# usb_hub_asic.net
KiCad netlist of a schematic drawn in EAGLE
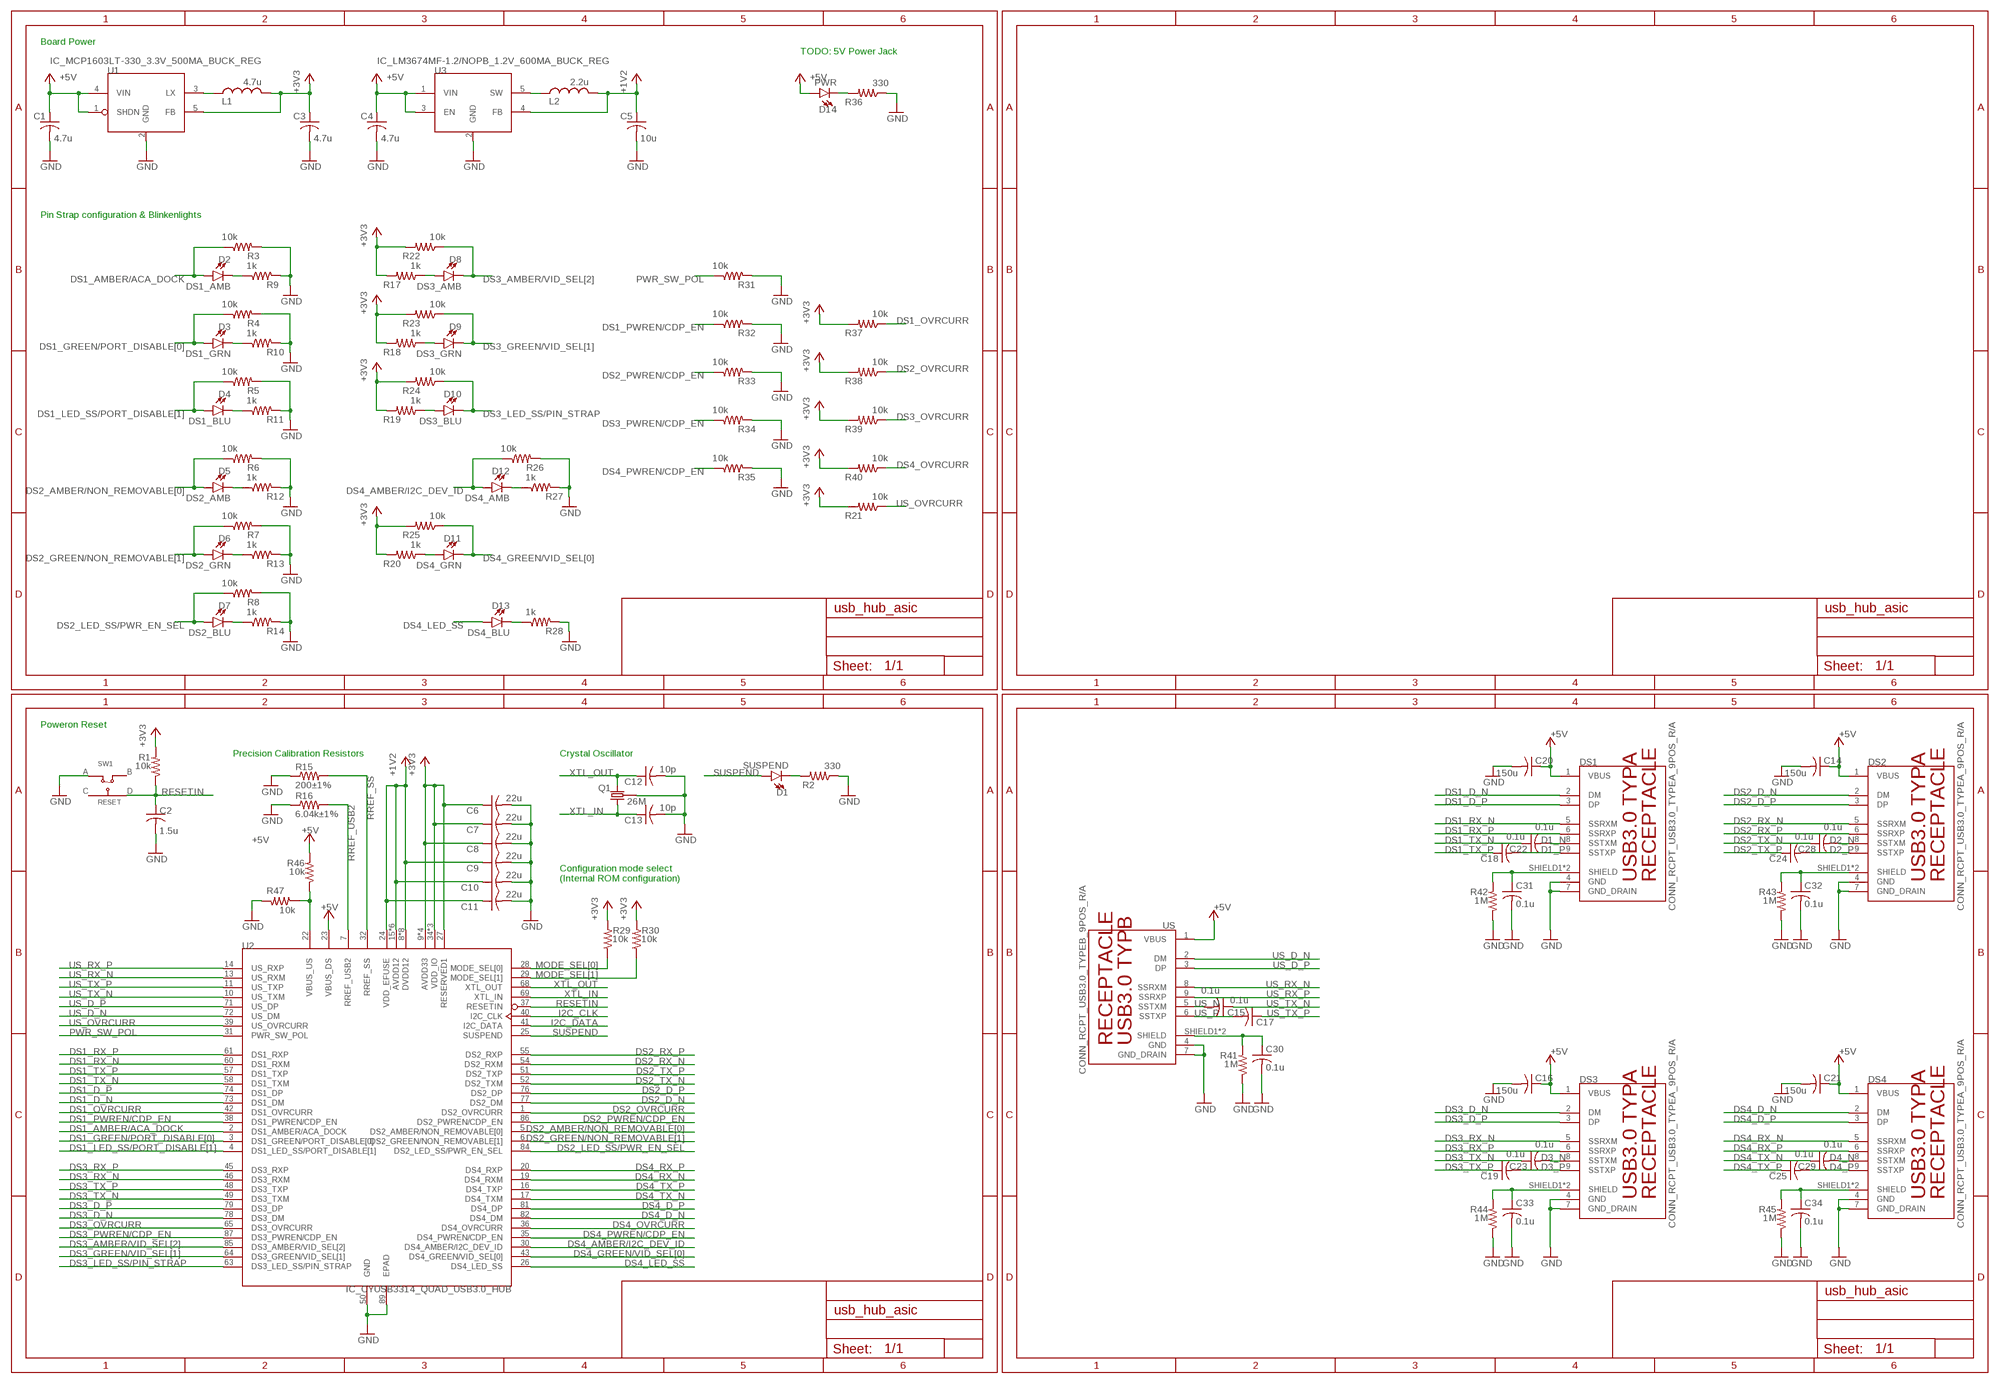
[diagram p0: schematic, sheet 1]

(export (version "E")
  (design (tool "Eeschema 10.0.6"))
  (components
    (comp (ref "C1")
      (value "4.7u")
      (footprint "eagle-import:C0603")
      (libsource (lib "eagle-import") (part "C-USC0603"))
    )
    (comp (ref "C2")
      (value "1.5u")
      (footprint "eagle-import:C0603")
      (libsource (lib "eagle-import") (part "C-USC0603"))
    )
    (comp (ref "C3")
      (value "4.7u")
      (footprint "eagle-import:C0603")
      (libsource (lib "eagle-import") (part "C-USC0603"))
    )
    (comp (ref "C4")
      (value "4.7u")
      (footprint "eagle-import:C0603")
      (libsource (lib "eagle-import") (part "C-USC0603"))
    )
    (comp (ref "C5")
      (value "10u")
      (footprint "eagle-import:C0805")
      (libsource (lib "eagle-import") (part "C-USC0805"))
    )
    (comp (ref "C6")
      (value "22u")
      (footprint "eagle-import:C0603")
      (libsource (lib "eagle-import") (part "C-USC0603"))
    )
    (comp (ref "C7")
      (value "22u")
      (footprint "eagle-import:C0603")
      (libsource (lib "eagle-import") (part "C-USC0603"))
    )
    (comp (ref "C8")
      (value "22u")
      (footprint "eagle-import:C0603")
      (libsource (lib "eagle-import") (part "C-USC0603"))
    )
    (comp (ref "C9")
      (value "22u")
      (footprint "eagle-import:C0603")
      (libsource (lib "eagle-import") (part "C-USC0603"))
    )
    (comp (ref "C10")
      (value "22u")
      (footprint "eagle-import:C0603")
      (libsource (lib "eagle-import") (part "C-USC0603"))
    )
    (comp (ref "C11")
      (value "22u")
      (footprint "eagle-import:C0603")
      (libsource (lib "eagle-import") (part "C-USC0603"))
    )
    (comp (ref "C12")
      (value "10p")
      (footprint "eagle-import:C0603")
      (libsource (lib "eagle-import") (part "C-USC0603"))
    )
    (comp (ref "C13")
      (value "10p")
      (footprint "eagle-import:C0603")
      (libsource (lib "eagle-import") (part "C-USC0603"))
    )
    (comp (ref "C14")
      (value "150u")
      (footprint "eagle-import:C1210K")
      (libsource (lib "eagle-import") (part "C-USC1210K"))
    )
    (comp (ref "C15")
      (value "0.1u")
      (footprint "eagle-import:C0603")
      (libsource (lib "eagle-import") (part "C-USC0603"))
    )
    (comp (ref "C16")
      (value "150u")
      (footprint "eagle-import:C1210K")
      (libsource (lib "eagle-import") (part "C-USC1210K"))
    )
    (comp (ref "C17")
      (value "0.1u")
      (footprint "eagle-import:C0603")
      (libsource (lib "eagle-import") (part "C-USC0603"))
    )
    (comp (ref "C18")
      (value "0.1u")
      (footprint "eagle-import:C0603")
      (libsource (lib "eagle-import") (part "C-USC0603"))
    )
    (comp (ref "C19")
      (value "0.1u")
      (footprint "eagle-import:C0603")
      (libsource (lib "eagle-import") (part "C-USC0603"))
    )
    (comp (ref "C20")
      (value "150u")
      (footprint "eagle-import:C1210K")
      (libsource (lib "eagle-import") (part "C-USC1210K"))
    )
    (comp (ref "C21")
      (value "150u")
      (footprint "eagle-import:C1210K")
      (libsource (lib "eagle-import") (part "C-USC1210K"))
    )
    (comp (ref "C22")
      (value "0.1u")
      (footprint "eagle-import:C0603")
      (libsource (lib "eagle-import") (part "C-USC0603"))
    )
    (comp (ref "C23")
      (value "0.1u")
      (footprint "eagle-import:C0603")
      (libsource (lib "eagle-import") (part "C-USC0603"))
    )
    (comp (ref "C24")
      (value "0.1u")
      (footprint "eagle-import:C0603")
      (libsource (lib "eagle-import") (part "C-USC0603"))
    )
    (comp (ref "C25")
      (value "0.1u")
      (footprint "eagle-import:C0603")
      (libsource (lib "eagle-import") (part "C-USC0603"))
    )
    (comp (ref "C28")
      (value "0.1u")
      (footprint "eagle-import:C0603")
      (libsource (lib "eagle-import") (part "C-USC0603"))
    )
    (comp (ref "C29")
      (value "0.1u")
      (footprint "eagle-import:C0603")
      (libsource (lib "eagle-import") (part "C-USC0603"))
    )
    (comp (ref "C30")
      (value "0.1u")
      (footprint "eagle-import:C0603")
      (libsource (lib "eagle-import") (part "C-USC0603"))
    )
    (comp (ref "C31")
      (value "0.1u")
      (footprint "eagle-import:C0603")
      (libsource (lib "eagle-import") (part "C-USC0603"))
    )
    (comp (ref "C32")
      (value "0.1u")
      (footprint "eagle-import:C0603")
      (libsource (lib "eagle-import") (part "C-USC0603"))
    )
    (comp (ref "C33")
      (value "0.1u")
      (footprint "eagle-import:C0603")
      (libsource (lib "eagle-import") (part "C-USC0603"))
    )
    (comp (ref "C34")
      (value "0.1u")
      (footprint "eagle-import:C0603")
      (libsource (lib "eagle-import") (part "C-USC0603"))
    )
    (comp (ref "D1")
      (value "SUSPEND")
      (footprint "eagle-import:LED-1206")
      (libsource (lib "eagle-import") (part "LED1206"))
    )
    (comp (ref "D2")
      (value "DS1_AMB")
      (footprint "eagle-import:LED-1206")
      (libsource (lib "eagle-import") (part "LED-RED1206"))
    )
    (comp (ref "D3")
      (value "DS1_GRN")
      (footprint "eagle-import:LED-1206")
      (libsource (lib "eagle-import") (part "LED-GREEN1206"))
    )
    (comp (ref "D4")
      (value "DS1_BLU")
      (footprint "eagle-import:LED-1206")
      (libsource (lib "eagle-import") (part "LED-BLUE1206"))
    )
    (comp (ref "D5")
      (value "DS2_AMB")
      (footprint "eagle-import:LED-1206")
      (libsource (lib "eagle-import") (part "LED-RED1206"))
    )
    (comp (ref "D6")
      (value "DS2_GRN")
      (footprint "eagle-import:LED-1206")
      (libsource (lib "eagle-import") (part "LED-GREEN1206"))
    )
    (comp (ref "D7")
      (value "DS2_BLU")
      (footprint "eagle-import:LED-1206")
      (libsource (lib "eagle-import") (part "LED-BLUE1206"))
    )
    (comp (ref "D8")
      (value "DS3_AMB")
      (footprint "eagle-import:LED-1206")
      (libsource (lib "eagle-import") (part "LED-RED1206"))
    )
    (comp (ref "D9")
      (value "DS3_GRN")
      (footprint "eagle-import:LED-1206")
      (libsource (lib "eagle-import") (part "LED-GREEN1206"))
    )
    (comp (ref "D10")
      (value "DS3_BLU")
      (footprint "eagle-import:LED-1206")
      (libsource (lib "eagle-import") (part "LED-BLUE1206"))
    )
    (comp (ref "D11")
      (value "DS4_GRN")
      (footprint "eagle-import:LED-1206")
      (libsource (lib "eagle-import") (part "LED-GREEN1206"))
    )
    (comp (ref "D12")
      (value "DS4_AMB")
      (footprint "eagle-import:LED-1206")
      (libsource (lib "eagle-import") (part "LED-RED1206"))
    )
    (comp (ref "D13")
      (value "DS4_BLU")
      (footprint "eagle-import:LED-1206")
      (libsource (lib "eagle-import") (part "LED-BLUE1206"))
    )
    (comp (ref "D14")
      (value "PWR")
      (footprint "eagle-import:LED-1206")
      (libsource (lib "eagle-import") (part "LED1206"))
    )
    (comp (ref "DS1")
      (value "CONN_RCPT_USB3.0_TYPEA_9POS_R/A")
      (footprint "eagle-import:CONN_RCPT_USB3.0_UJ3-AH-4-TH")
      (libsource (lib "eagle-import") (part "CONN_RCPT_USB3.0_TYPEA_9POS_R/A"))
    )
    (comp (ref "DS2")
      (value "CONN_RCPT_USB3.0_TYPEA_9POS_R/A")
      (footprint "eagle-import:CONN_RCPT_USB3.0_UJ3-AH-4-TH")
      (libsource (lib "eagle-import") (part "CONN_RCPT_USB3.0_TYPEA_9POS_R/A"))
    )
    (comp (ref "DS3")
      (value "CONN_RCPT_USB3.0_TYPEA_9POS_R/A")
      (footprint "eagle-import:CONN_RCPT_USB3.0_UJ3-AH-4-TH")
      (libsource (lib "eagle-import") (part "CONN_RCPT_USB3.0_TYPEA_9POS_R/A"))
    )
    (comp (ref "DS4")
      (value "CONN_RCPT_USB3.0_TYPEA_9POS_R/A")
      (footprint "eagle-import:CONN_RCPT_USB3.0_UJ3-AH-4-TH")
      (libsource (lib "eagle-import") (part "CONN_RCPT_USB3.0_TYPEA_9POS_R/A"))
    )
    (comp (ref "L1")
      (value "4.7u")
      (footprint "eagle-import:SMD-1212(3030METRIC)")
      (libsource (lib "eagle-import") (part "L_4.7UH_1.5A_SMD_1212(3030METRIC)"))
    )
    (comp (ref "L2")
      (value "2.2u")
      (footprint "eagle-import:SMD-0805(2012METRIC)")
      (libsource (lib "eagle-import") (part "L_2.2UH_1.3A_SMD_0805(2012METRIC)"))
    )
    (comp (ref "Q1")
      (value "26M")
      (footprint "eagle-import:4-SMD-ECS-260-13-42-CKM-TR")
      (libsource (lib "eagle-import") (part "XTAL_26MHZ_4-SMD_ECX-42"))
    )
    (comp (ref "R1")
      (value "10k")
      (footprint "eagle-import:R0603")
      (libsource (lib "eagle-import") (part "R-US_R0603"))
    )
    (comp (ref "R2")
      (value "330")
      (footprint "eagle-import:R0603")
      (libsource (lib "eagle-import") (part "R-US_R0603"))
    )
    (comp (ref "R3")
      (value "10k")
      (footprint "eagle-import:R0603")
      (libsource (lib "eagle-import") (part "R-US_R0603"))
    )
    (comp (ref "R4")
      (value "10k")
      (footprint "eagle-import:R0603")
      (libsource (lib "eagle-import") (part "R-US_R0603"))
    )
    (comp (ref "R5")
      (value "10k")
      (footprint "eagle-import:R0603")
      (libsource (lib "eagle-import") (part "R-US_R0603"))
    )
    (comp (ref "R6")
      (value "10k")
      (footprint "eagle-import:R0603")
      (libsource (lib "eagle-import") (part "R-US_R0603"))
    )
    (comp (ref "R7")
      (value "10k")
      (footprint "eagle-import:R0603")
      (libsource (lib "eagle-import") (part "R-US_R0603"))
    )
    (comp (ref "R8")
      (value "10k")
      (footprint "eagle-import:R0603")
      (libsource (lib "eagle-import") (part "R-US_R0603"))
    )
    (comp (ref "R9")
      (value "1k")
      (footprint "eagle-import:R0603")
      (libsource (lib "eagle-import") (part "R-US_R0603"))
    )
    (comp (ref "R10")
      (value "1k")
      (footprint "eagle-import:R0603")
      (libsource (lib "eagle-import") (part "R-US_R0603"))
    )
    (comp (ref "R11")
      (value "1k")
      (footprint "eagle-import:R0603")
      (libsource (lib "eagle-import") (part "R-US_R0603"))
    )
    (comp (ref "R12")
      (value "1k")
      (footprint "eagle-import:R0603")
      (libsource (lib "eagle-import") (part "R-US_R0603"))
    )
    (comp (ref "R13")
      (value "1k")
      (footprint "eagle-import:R0603")
      (libsource (lib "eagle-import") (part "R-US_R0603"))
    )
    (comp (ref "R14")
      (value "1k")
      (footprint "eagle-import:R0603")
      (libsource (lib "eagle-import") (part "R-US_R0603"))
    )
    (comp (ref "R15")
      (value "200±1%")
      (footprint "eagle-import:R0603")
      (libsource (lib "eagle-import") (part "R-US_R0603"))
    )
    (comp (ref "R16")
      (value "6.04k±1%")
      (footprint "eagle-import:R0603")
      (libsource (lib "eagle-import") (part "R-US_R0603"))
    )
    (comp (ref "R17")
      (value "1k")
      (footprint "eagle-import:R0603")
      (libsource (lib "eagle-import") (part "R-US_R0603"))
    )
    (comp (ref "R18")
      (value "1k")
      (footprint "eagle-import:R0603")
      (libsource (lib "eagle-import") (part "R-US_R0603"))
    )
    (comp (ref "R19")
      (value "1k")
      (footprint "eagle-import:R0603")
      (libsource (lib "eagle-import") (part "R-US_R0603"))
    )
    (comp (ref "R20")
      (value "1k")
      (footprint "eagle-import:R0603")
      (libsource (lib "eagle-import") (part "R-US_R0603"))
    )
    (comp (ref "R21")
      (value "10k")
      (footprint "eagle-import:R0603")
      (libsource (lib "eagle-import") (part "R-US_R0603"))
    )
    (comp (ref "R22")
      (value "10k")
      (footprint "eagle-import:R0603")
      (libsource (lib "eagle-import") (part "R-US_R0603"))
    )
    (comp (ref "R23")
      (value "10k")
      (footprint "eagle-import:R0603")
      (libsource (lib "eagle-import") (part "R-US_R0603"))
    )
    (comp (ref "R24")
      (value "10k")
      (footprint "eagle-import:R0603")
      (libsource (lib "eagle-import") (part "R-US_R0603"))
    )
    (comp (ref "R25")
      (value "10k")
      (footprint "eagle-import:R0603")
      (libsource (lib "eagle-import") (part "R-US_R0603"))
    )
    (comp (ref "R26")
      (value "10k")
      (footprint "eagle-import:R0603")
      (libsource (lib "eagle-import") (part "R-US_R0603"))
    )
    (comp (ref "R27")
      (value "1k")
      (footprint "eagle-import:R0603")
      (libsource (lib "eagle-import") (part "R-US_R0603"))
    )
    (comp (ref "R28")
      (value "1k")
      (footprint "eagle-import:R0603")
      (libsource (lib "eagle-import") (part "R-US_R0603"))
    )
    (comp (ref "R29")
      (value "10k")
      (footprint "eagle-import:R0603")
      (libsource (lib "eagle-import") (part "R-US_R0603"))
    )
    (comp (ref "R30")
      (value "10k")
      (footprint "eagle-import:R0603")
      (libsource (lib "eagle-import") (part "R-US_R0603"))
    )
    (comp (ref "R31")
      (value "10k")
      (footprint "eagle-import:R0603")
      (libsource (lib "eagle-import") (part "R-US_R0603"))
    )
    (comp (ref "R32")
      (value "10k")
      (footprint "eagle-import:R0603")
      (libsource (lib "eagle-import") (part "R-US_R0603"))
    )
    (comp (ref "R33")
      (value "10k")
      (footprint "eagle-import:R0603")
      (libsource (lib "eagle-import") (part "R-US_R0603"))
    )
    (comp (ref "R34")
      (value "10k")
      (footprint "eagle-import:R0603")
      (libsource (lib "eagle-import") (part "R-US_R0603"))
    )
    (comp (ref "R35")
      (value "10k")
      (footprint "eagle-import:R0603")
      (libsource (lib "eagle-import") (part "R-US_R0603"))
    )
    (comp (ref "R36")
      (value "330")
      (footprint "eagle-import:R0603")
      (libsource (lib "eagle-import") (part "R-US_R0603"))
    )
    (comp (ref "R37")
      (value "10k")
      (footprint "eagle-import:R0603")
      (libsource (lib "eagle-import") (part "R-US_R0603"))
    )
    (comp (ref "R38")
      (value "10k")
      (footprint "eagle-import:R0603")
      (libsource (lib "eagle-import") (part "R-US_R0603"))
    )
    (comp (ref "R39")
      (value "10k")
      (footprint "eagle-import:R0603")
      (libsource (lib "eagle-import") (part "R-US_R0603"))
    )
    (comp (ref "R40")
      (value "10k")
      (footprint "eagle-import:R0603")
      (libsource (lib "eagle-import") (part "R-US_R0603"))
    )
    (comp (ref "R41")
      (value "1M")
      (footprint "eagle-import:R0603")
      (libsource (lib "eagle-import") (part "R-US_R0603"))
    )
    (comp (ref "R42")
      (value "1M")
      (footprint "eagle-import:R0603")
      (libsource (lib "eagle-import") (part "R-US_R0603"))
    )
    (comp (ref "R43")
      (value "1M")
      (footprint "eagle-import:R0603")
      (libsource (lib "eagle-import") (part "R-US_R0603"))
    )
    (comp (ref "R44")
      (value "1M")
      (footprint "eagle-import:R0603")
      (libsource (lib "eagle-import") (part "R-US_R0603"))
    )
    (comp (ref "R45")
      (value "1M")
      (footprint "eagle-import:R0603")
      (libsource (lib "eagle-import") (part "R-US_R0603"))
    )
    (comp (ref "R46")
      (value "10k")
      (footprint "eagle-import:R0603")
      (libsource (lib "eagle-import") (part "R-US_R0603"))
    )
    (comp (ref "R47")
      (value "10k")
      (footprint "eagle-import:R0603")
      (libsource (lib "eagle-import") (part "R-US_R0603"))
    )
    (comp (ref "SW1")
      (value "RESET")
      (footprint "eagle-import:SMD-TLSMDT3C020GLFS")
      (libsource (lib "eagle-import") (part "SW_SPDT_TLSMDT3C020GLFS"))
    )
    (comp (ref "U1")
      (value "IC_MCP1603LT-330_3.3V_500MA_BUCK_REG")
      (footprint "eagle-import:5-TSOT23")
      (libsource (lib "eagle-import") (part "IC_MCP1603LT-330_3.3V_500MA_BUCK_REG"))
    )
    (comp (ref "U2")
      (value "IC_CYUSB3314_QUAD_USB3.0_HUB")
      (footprint "eagle-import:88-QFN_10X10X1_5.3_TPAD")
      (libsource (lib "eagle-import") (part "IC_CYUSB3314_QUAD_USB3.0_HUB"))
    )
    (comp (ref "U3")
      (value "IC_LM3674MF-1.2/NOPB_1.2V_600MA_BUCK_REG")
      (footprint "eagle-import:5-TSOT23")
      (libsource (lib "eagle-import") (part "IC_LM3674MF-1.2/NOPB_1.2V_600MA_BUCK_REG"))
    )
    (comp (ref "US")
      (value "CONN_RCPT_USB3.0_TYPEB_9POS_R/A")
      (footprint "eagle-import:CONN_RCPT_USB3.0_E8199-030-03")
      (libsource (lib "eagle-import") (part "CONN_RCPT_USB3.0_TYPEB_9POS_R/A"))
    )
  )
  (nets
    (net (code "1") (name "+1V2") (class "Default")
      (node (ref "C10") (pin "1") (pinfunction "1_1") (pintype "passive"))
      (node (ref "C11") (pin "1") (pinfunction "1_1") (pintype "passive"))
      (node (ref "C5") (pin "1") (pinfunction "1_1") (pintype "passive"))
      (node (ref "C9") (pin "1") (pinfunction "1_1") (pintype "passive"))
      (node (ref "L2") (pin "P$2") (pinfunction "2_P$2") (pintype "passive"))
      (node (ref "U2") (pin "12") (pinfunction "DVDD12_12") (pintype "power_in"))
      (node (ref "U2") (pin "15") (pinfunction "AVDD12_15") (pintype "power_in"))
      (node (ref "U2") (pin "18") (pinfunction "DVDD12_18") (pintype "power_in"))
      (node (ref "U2") (pin "21") (pinfunction "AVDD12_21") (pintype "power_in"))
      (node (ref "U2") (pin "24") (pinfunction "VDD_EFUSE_24") (pintype "power_in"))
      (node (ref "U2") (pin "33") (pinfunction "DVDD12_33") (pintype "power_in"))
      (node (ref "U2") (pin "44") (pinfunction "AVDD12_44") (pintype "power_in"))
      (node (ref "U2") (pin "47") (pinfunction "DVDD12_47") (pintype "power_in"))
      (node (ref "U2") (pin "53") (pinfunction "DVDD12_53") (pintype "power_in"))
      (node (ref "U2") (pin "56") (pinfunction "AVDD12_56") (pintype "power_in"))
      (node (ref "U2") (pin "59") (pinfunction "DVDD12_59") (pintype "power_in"))
      (node (ref "U2") (pin "62") (pinfunction "AVDD12_62") (pintype "power_in"))
      (node (ref "U2") (pin "67") (pinfunction "AVDD12_67") (pintype "power_in"))
      (node (ref "U2") (pin "8") (pinfunction "DVDD12_8") (pintype "power_in"))
      (node (ref "U2") (pin "83") (pinfunction "DVDD12_83") (pintype "power_in"))
      (node (ref "U3") (pin "4") (pinfunction "FB_4") (pintype "input"))
    )
    (net (code "2") (name "+3V3") (class "Default")
      (node (ref "C3") (pin "1") (pinfunction "1_1") (pintype "passive"))
      (node (ref "C6") (pin "1") (pinfunction "1_1") (pintype "passive"))
      (node (ref "C7") (pin "1") (pinfunction "1_1") (pintype "passive"))
      (node (ref "C8") (pin "1") (pinfunction "1_1") (pintype "passive"))
      (node (ref "L1") (pin "P$2") (pinfunction "2_P$2") (pintype "passive"))
      (node (ref "R1") (pin "2") (pinfunction "2_2") (pintype "passive"))
      (node (ref "R17") (pin "2") (pinfunction "2_2") (pintype "passive"))
      (node (ref "R18") (pin "2") (pinfunction "2_2") (pintype "passive"))
      (node (ref "R19") (pin "2") (pinfunction "2_2") (pintype "passive"))
      (node (ref "R20") (pin "2") (pinfunction "2_2") (pintype "passive"))
      (node (ref "R21") (pin "2") (pinfunction "2_2") (pintype "passive"))
      (node (ref "R22") (pin "2") (pinfunction "2_2") (pintype "passive"))
      (node (ref "R23") (pin "2") (pinfunction "2_2") (pintype "passive"))
      (node (ref "R24") (pin "2") (pinfunction "2_2") (pintype "passive"))
      (node (ref "R25") (pin "2") (pinfunction "2_2") (pintype "passive"))
      (node (ref "R29") (pin "2") (pinfunction "2_2") (pintype "passive"))
      (node (ref "R30") (pin "2") (pinfunction "2_2") (pintype "passive"))
      (node (ref "R37") (pin "2") (pinfunction "2_2") (pintype "passive"))
      (node (ref "R38") (pin "2") (pinfunction "2_2") (pintype "passive"))
      (node (ref "R39") (pin "2") (pinfunction "2_2") (pintype "passive"))
      (node (ref "R40") (pin "2") (pinfunction "2_2") (pintype "passive"))
      (node (ref "U1") (pin "5") (pinfunction "FB_5") (pintype "input"))
      (node (ref "U2") (pin "27") (pinfunction "RESERVED1_27") (pintype "input"))
      (node (ref "U2") (pin "34") (pinfunction "VDD_IO_34") (pintype "power_in"))
      (node (ref "U2") (pin "66") (pinfunction "VDD_IO_66") (pintype "power_in"))
      (node (ref "U2") (pin "70") (pinfunction "AVDD33_70") (pintype "power_in"))
      (node (ref "U2") (pin "75") (pinfunction "AVDD33_75") (pintype "power_in"))
      (node (ref "U2") (pin "80") (pinfunction "AVDD33_80") (pintype "power_in"))
      (node (ref "U2") (pin "88") (pinfunction "VDD_IO_88") (pintype "power_in"))
      (node (ref "U2") (pin "9") (pinfunction "AVDD33_9") (pintype "power_in"))
    )
    (net (code "3") (name "+5V") (class "Default")
      (node (ref "C1") (pin "1") (pinfunction "1_1") (pintype "passive"))
      (node (ref "C14") (pin "1") (pinfunction "1_1") (pintype "passive"))
      (node (ref "C16") (pin "1") (pinfunction "1_1") (pintype "passive"))
      (node (ref "C20") (pin "1") (pinfunction "1_1") (pintype "passive"))
      (node (ref "C21") (pin "1") (pinfunction "1_1") (pintype "passive"))
      (node (ref "C4") (pin "1") (pinfunction "1_1") (pintype "passive"))
      (node (ref "D14") (pin "A") (pinfunction "A_A") (pintype "passive"))
      (node (ref "DS1") (pin "1") (pinfunction "VBUS_1") (pintype "power_in"))
      (node (ref "DS2") (pin "1") (pinfunction "VBUS_1") (pintype "power_in"))
      (node (ref "DS3") (pin "1") (pinfunction "VBUS_1") (pintype "power_in"))
      (node (ref "DS4") (pin "1") (pinfunction "VBUS_1") (pintype "power_in"))
      (node (ref "R46") (pin "2") (pinfunction "2_2") (pintype "passive"))
      (node (ref "U1") (pin "1") (pinfunction "SHDN_1") (pintype "input"))
      (node (ref "U1") (pin "4") (pinfunction "VIN_4") (pintype "power_in"))
      (node (ref "U2") (pin "23") (pinfunction "VBUS_DS_23") (pintype "power_in"))
      (node (ref "U3") (pin "1") (pinfunction "VIN_1") (pintype "power_in"))
      (node (ref "U3") (pin "3") (pinfunction "EN_3") (pintype "input"))
      (node (ref "US") (pin "1") (pinfunction "VBUS_1") (pintype "power_in"))
    )
    (net (code "4") (name "/D1_N") (class "Default")
      (node (ref "C22") (pin "2") (pinfunction "2_2") (pintype "passive"))
      (node (ref "DS1") (pin "8") (pinfunction "SSTXM_8") (pintype "input"))
    )
    (net (code "5") (name "/D1_P") (class "Default")
      (node (ref "C18") (pin "2") (pinfunction "2_2") (pintype "passive"))
      (node (ref "DS1") (pin "9") (pinfunction "SSTXP_9") (pintype "input"))
    )
    (net (code "6") (name "/D2_N") (class "Default")
      (node (ref "C28") (pin "2") (pinfunction "2_2") (pintype "passive"))
      (node (ref "DS2") (pin "8") (pinfunction "SSTXM_8") (pintype "input"))
    )
    (net (code "7") (name "/D2_P") (class "Default")
      (node (ref "C24") (pin "2") (pinfunction "2_2") (pintype "passive"))
      (node (ref "DS2") (pin "9") (pinfunction "SSTXP_9") (pintype "input"))
    )
    (net (code "8") (name "/D3_N") (class "Default")
      (node (ref "C23") (pin "2") (pinfunction "2_2") (pintype "passive"))
      (node (ref "DS3") (pin "8") (pinfunction "SSTXM_8") (pintype "input"))
    )
    (net (code "9") (name "/D3_P") (class "Default")
      (node (ref "C19") (pin "2") (pinfunction "2_2") (pintype "passive"))
      (node (ref "DS3") (pin "9") (pinfunction "SSTXP_9") (pintype "input"))
    )
    (net (code "10") (name "/D4_N") (class "Default")
      (node (ref "C29") (pin "2") (pinfunction "2_2") (pintype "passive"))
      (node (ref "DS4") (pin "8") (pinfunction "SSTXM_8") (pintype "input"))
    )
    (net (code "11") (name "/D4_P") (class "Default")
      (node (ref "C25") (pin "2") (pinfunction "2_2") (pintype "passive"))
      (node (ref "DS4") (pin "9") (pinfunction "SSTXP_9") (pintype "input"))
    )
    (net (code "12") (name "/DS1_AMBER{slash}ACA_DOCK") (class "Default")
      (node (ref "D2") (pin "A") (pinfunction "A_A") (pintype "passive"))
      (node (ref "R3") (pin "1") (pinfunction "1_1") (pintype "passive"))
      (node (ref "U2") (pin "2") (pinfunction "DS1_AMBER/ACA_DOCK_2") (pintype "bidirectional"))
    )
    (net (code "13") (name "/DS1_D_N") (class "Default")
      (node (ref "DS1") (pin "2") (pinfunction "DM_2") (pintype "bidirectional"))
      (node (ref "U2") (pin "73") (pinfunction "DS1_DM_73") (pintype "bidirectional"))
    )
    (net (code "14") (name "/DS1_D_P") (class "Default")
      (node (ref "DS1") (pin "3") (pinfunction "DP_3") (pintype "bidirectional"))
      (node (ref "U2") (pin "74") (pinfunction "DS1_DP_74") (pintype "bidirectional"))
    )
    (net (code "15") (name "/DS1_GREEN{slash}PORT_DISABLE[0]") (class "Default")
      (node (ref "D3") (pin "A") (pinfunction "A_A") (pintype "passive"))
      (node (ref "R4") (pin "1") (pinfunction "1_1") (pintype "passive"))
      (node (ref "U2") (pin "3") (pinfunction "DS1_GREEN/PORT_DISABLE[0]_3") (pintype "bidirectional"))
    )
    (net (code "16") (name "/DS1_LED_SS{slash}PORT_DISABLE[1]") (class "Default")
      (node (ref "D4") (pin "A") (pinfunction "A_A") (pintype "passive"))
      (node (ref "R5") (pin "1") (pinfunction "1_1") (pintype "passive"))
      (node (ref "U2") (pin "4") (pinfunction "DS1_LED_SS/PORT_DISABLE[1]_4") (pintype "bidirectional"))
    )
    (net (code "17") (name "/DS1_OVRCURR") (class "Default")
      (node (ref "R37") (pin "1") (pinfunction "1_1") (pintype "passive"))
      (node (ref "U2") (pin "42") (pinfunction "DS1_OVRCURR_42") (pintype "input"))
    )
    (net (code "18") (name "/DS1_PWREN{slash}CDP_EN") (class "Default")
      (node (ref "R32") (pin "1") (pinfunction "1_1") (pintype "passive"))
      (node (ref "U2") (pin "38") (pinfunction "DS1_PWREN/CDP_EN_38") (pintype "bidirectional"))
    )
    (net (code "19") (name "/DS1_RX_N") (class "Default")
      (node (ref "DS1") (pin "5") (pinfunction "SSRXM_5") (pintype "output"))
      (node (ref "U2") (pin "60") (pinfunction "DS1_RXM_60") (pintype "input"))
    )
    (net (code "20") (name "/DS1_RX_P") (class "Default")
      (node (ref "DS1") (pin "6") (pinfunction "SSRXP_6") (pintype "output"))
      (node (ref "U2") (pin "61") (pinfunction "DS1_RXP_61") (pintype "input"))
    )
    (net (code "21") (name "/DS1_TX_N") (class "Default")
      (node (ref "C22") (pin "1") (pinfunction "1_1") (pintype "passive"))
      (node (ref "U2") (pin "58") (pinfunction "DS1_TXM_58") (pintype "output"))
    )
    (net (code "22") (name "/DS1_TX_P") (class "Default")
      (node (ref "C18") (pin "1") (pinfunction "1_1") (pintype "passive"))
      (node (ref "U2") (pin "57") (pinfunction "DS1_TXP_57") (pintype "output"))
    )
    (net (code "23") (name "/DS2_AMBER{slash}NON_REMOVABLE[0]") (class "Default")
      (node (ref "D5") (pin "A") (pinfunction "A_A") (pintype "passive"))
      (node (ref "R6") (pin "1") (pinfunction "1_1") (pintype "passive"))
      (node (ref "U2") (pin "5") (pinfunction "DS2_AMBER/NON_REMOVABLE[0]_5") (pintype "bidirectional"))
    )
    (net (code "24") (name "/DS2_D_N") (class "Default")
      (node (ref "DS2") (pin "2") (pinfunction "DM_2") (pintype "bidirectional"))
      (node (ref "U2") (pin "77") (pinfunction "DS2_DM_77") (pintype "bidirectional"))
    )
    (net (code "25") (name "/DS2_D_P") (class "Default")
      (node (ref "DS2") (pin "3") (pinfunction "DP_3") (pintype "bidirectional"))
      (node (ref "U2") (pin "76") (pinfunction "DS2_DP_76") (pintype "bidirectional"))
    )
    (net (code "26") (name "/DS2_GREEN{slash}NON_REMOVABLE[1]") (class "Default")
      (node (ref "D6") (pin "A") (pinfunction "A_A") (pintype "passive"))
      (node (ref "R7") (pin "1") (pinfunction "1_1") (pintype "passive"))
      (node (ref "U2") (pin "6") (pinfunction "DS2_GREEN/NON_REMOVABLE[1]_6") (pintype "bidirectional"))
    )
    (net (code "27") (name "/DS2_LED_SS{slash}PWR_EN_SEL") (class "Default")
      (node (ref "D7") (pin "A") (pinfunction "A_A") (pintype "passive"))
      (node (ref "R8") (pin "1") (pinfunction "1_1") (pintype "passive"))
      (node (ref "U2") (pin "84") (pinfunction "DS2_LED_SS/PWR_EN_SEL_84") (pintype "bidirectional"))
    )
    (net (code "28") (name "/DS2_OVRCURR") (class "Default")
      (node (ref "R38") (pin "1") (pinfunction "1_1") (pintype "passive"))
      (node (ref "U2") (pin "1") (pinfunction "DS2_OVRCURR_1") (pintype "input"))
    )
    (net (code "29") (name "/DS2_PWREN{slash}CDP_EN") (class "Default")
      (node (ref "R33") (pin "1") (pinfunction "1_1") (pintype "passive"))
      (node (ref "U2") (pin "86") (pinfunction "DS2_PWREN/CDP_EN_86") (pintype "bidirectional"))
    )
    (net (code "30") (name "/DS2_RX_N") (class "Default")
      (node (ref "DS2") (pin "5") (pinfunction "SSRXM_5") (pintype "output"))
      (node (ref "U2") (pin "54") (pinfunction "DS2_RXM_54") (pintype "input"))
    )
    (net (code "31") (name "/DS2_RX_P") (class "Default")
      (node (ref "DS2") (pin "6") (pinfunction "SSRXP_6") (pintype "output"))
      (node (ref "U2") (pin "55") (pinfunction "DS2_RXP_55") (pintype "input"))
    )
    (net (code "32") (name "/DS2_TX_N") (class "Default")
      (node (ref "C28") (pin "1") (pinfunction "1_1") (pintype "passive"))
      (node (ref "U2") (pin "52") (pinfunction "DS2_TXM_52") (pintype "output"))
    )
    (net (code "33") (name "/DS2_TX_P") (class "Default")
      (node (ref "C24") (pin "1") (pinfunction "1_1") (pintype "passive"))
      (node (ref "U2") (pin "51") (pinfunction "DS2_TXP_51") (pintype "output"))
    )
    (net (code "34") (name "/DS3_AMBER{slash}VID_SEL[2]") (class "Default")
      (node (ref "D8") (pin "C") (pinfunction "C_C") (pintype "passive"))
      (node (ref "R22") (pin "1") (pinfunction "1_1") (pintype "passive"))
      (node (ref "U2") (pin "85") (pinfunction "DS3_AMBER/VID_SEL[2]_85") (pintype "bidirectional"))
    )
    (net (code "35") (name "/DS3_D_N") (class "Default")
      (node (ref "DS3") (pin "2") (pinfunction "DM_2") (pintype "bidirectional"))
      (node (ref "U2") (pin "78") (pinfunction "DS3_DM_78") (pintype "bidirectional"))
    )
    (net (code "36") (name "/DS3_D_P") (class "Default")
      (node (ref "DS3") (pin "3") (pinfunction "DP_3") (pintype "bidirectional"))
      (node (ref "U2") (pin "79") (pinfunction "DS3_DP_79") (pintype "bidirectional"))
    )
    (net (code "37") (name "/DS3_GREEN{slash}VID_SEL[1]") (class "Default")
      (node (ref "D9") (pin "C") (pinfunction "C_C") (pintype "passive"))
      (node (ref "R23") (pin "1") (pinfunction "1_1") (pintype "passive"))
      (node (ref "U2") (pin "64") (pinfunction "DS3_GREEN/VID_SEL[1]_64") (pintype "bidirectional"))
    )
    (net (code "38") (name "/DS3_LED_SS{slash}PIN_STRAP") (class "Default")
      (node (ref "D10") (pin "C") (pinfunction "C_C") (pintype "passive"))
      (node (ref "R24") (pin "1") (pinfunction "1_1") (pintype "passive"))
      (node (ref "U2") (pin "63") (pinfunction "DS3_LED_SS/PIN_STRAP_63") (pintype "bidirectional"))
    )
    (net (code "39") (name "/DS3_OVRCURR") (class "Default")
      (node (ref "R39") (pin "1") (pinfunction "1_1") (pintype "passive"))
      (node (ref "U2") (pin "65") (pinfunction "DS3_OVRCURR_65") (pintype "input"))
    )
    (net (code "40") (name "/DS3_PWREN{slash}CDP_EN") (class "Default")
      (node (ref "R34") (pin "1") (pinfunction "1_1") (pintype "passive"))
      (node (ref "U2") (pin "87") (pinfunction "DS3_PWREN/CDP_EN_87") (pintype "bidirectional"))
    )
    (net (code "41") (name "/DS3_RX_N") (class "Default")
      (node (ref "DS3") (pin "5") (pinfunction "SSRXM_5") (pintype "output"))
      (node (ref "U2") (pin "46") (pinfunction "DS3_RXM_46") (pintype "input"))
    )
    (net (code "42") (name "/DS3_RX_P") (class "Default")
      (node (ref "DS3") (pin "6") (pinfunction "SSRXP_6") (pintype "output"))
      (node (ref "U2") (pin "45") (pinfunction "DS3_RXP_45") (pintype "input"))
    )
    (net (code "43") (name "/DS3_TX_N") (class "Default")
      (node (ref "C23") (pin "1") (pinfunction "1_1") (pintype "passive"))
      (node (ref "U2") (pin "49") (pinfunction "DS3_TXM_49") (pintype "output"))
    )
    (net (code "44") (name "/DS3_TX_P") (class "Default")
      (node (ref "C19") (pin "1") (pinfunction "1_1") (pintype "passive"))
      (node (ref "U2") (pin "48") (pinfunction "DS3_TXP_48") (pintype "output"))
    )
    (net (code "45") (name "/DS4_AMBER{slash}I2C_DEV_ID") (class "Default")
      (node (ref "D12") (pin "A") (pinfunction "A_A") (pintype "passive"))
      (node (ref "R26") (pin "1") (pinfunction "1_1") (pintype "passive"))
      (node (ref "U2") (pin "30") (pinfunction "DS4_AMBER/I2C_DEV_ID_30") (pintype "bidirectional"))
    )
    (net (code "46") (name "/DS4_D_N") (class "Default")
      (node (ref "DS4") (pin "2") (pinfunction "DM_2") (pintype "bidirectional"))
      (node (ref "U2") (pin "82") (pinfunction "DS4_DM_82") (pintype "bidirectional"))
    )
    (net (code "47") (name "/DS4_D_P") (class "Default")
      (node (ref "DS4") (pin "3") (pinfunction "DP_3") (pintype "bidirectional"))
      (node (ref "U2") (pin "81") (pinfunction "DS4_DP_81") (pintype "bidirectional"))
    )
    (net (code "48") (name "/DS4_GREEN{slash}VID_SEL[0]") (class "Default")
      (node (ref "D11") (pin "C") (pinfunction "C_C") (pintype "passive"))
      (node (ref "R25") (pin "1") (pinfunction "1_1") (pintype "passive"))
      (node (ref "U2") (pin "43") (pinfunction "DS4_GREEN/VID_SEL[0]_43") (pintype "bidirectional"))
    )
    (net (code "49") (name "/DS4_LED_SS") (class "Default")
      (node (ref "D13") (pin "A") (pinfunction "A_A") (pintype "passive"))
      (node (ref "U2") (pin "26") (pinfunction "DS4_LED_SS_26") (pintype "bidirectional"))
    )
    (net (code "50") (name "/DS4_OVRCURR") (class "Default")
      (node (ref "R40") (pin "1") (pinfunction "1_1") (pintype "passive"))
      (node (ref "U2") (pin "36") (pinfunction "DS4_OVRCURR_36") (pintype "input"))
    )
    (net (code "51") (name "/DS4_PWREN{slash}CDP_EN") (class "Default")
      (node (ref "R35") (pin "1") (pinfunction "1_1") (pintype "passive"))
      (node (ref "U2") (pin "35") (pinfunction "DS4_PWREN/CDP_EN_35") (pintype "bidirectional"))
    )
    (net (code "52") (name "/DS4_RX_N") (class "Default")
      (node (ref "DS4") (pin "5") (pinfunction "SSRXM_5") (pintype "output"))
      (node (ref "U2") (pin "19") (pinfunction "DS4_RXM_19") (pintype "input"))
    )
    (net (code "53") (name "/DS4_RX_P") (class "Default")
      (node (ref "DS4") (pin "6") (pinfunction "SSRXP_6") (pintype "output"))
      (node (ref "U2") (pin "20") (pinfunction "DS4_RXP_20") (pintype "input"))
    )
    (net (code "54") (name "/DS4_TX_N") (class "Default")
      (node (ref "C29") (pin "1") (pinfunction "1_1") (pintype "passive"))
      (node (ref "U2") (pin "17") (pinfunction "DS4_TXM_17") (pintype "output"))
    )
    (net (code "55") (name "/DS4_TX_P") (class "Default")
      (node (ref "C25") (pin "1") (pinfunction "1_1") (pintype "passive"))
      (node (ref "U2") (pin "16") (pinfunction "DS4_TXP_16") (pintype "output"))
    )
    (net (code "56") (name "/I2C_CLK") (class "Default")
      (node (ref "U2") (pin "40") (pinfunction "I2C_CLK_40") (pintype "bidirectional"))
    )
    (net (code "57") (name "/I2C_DATA") (class "Default")
      (node (ref "U2") (pin "41") (pinfunction "I2C_DATA_41") (pintype "bidirectional"))
    )
    (net (code "58") (name "/MODE_SEL[0]") (class "Default")
      (node (ref "R29") (pin "1") (pinfunction "1_1") (pintype "passive"))
      (node (ref "U2") (pin "28") (pinfunction "MODE_SEL[0]_28") (pintype "input"))
    )
    (net (code "59") (name "/MODE_SEL[1]") (class "Default")
      (node (ref "R30") (pin "1") (pinfunction "1_1") (pintype "passive"))
      (node (ref "U2") (pin "29") (pinfunction "MODE_SEL[1]_29") (pintype "input"))
    )
    (net (code "60") (name "/PWR_SW_POL") (class "Default")
      (node (ref "R31") (pin "1") (pinfunction "1_1") (pintype "passive"))
      (node (ref "U2") (pin "31") (pinfunction "PWR_SW_POL_31") (pintype "bidirectional"))
    )
    (net (code "61") (name "/RESETIN") (class "Default")
      (node (ref "C2") (pin "1") (pinfunction "1_1") (pintype "passive"))
      (node (ref "R1") (pin "1") (pinfunction "1_1") (pintype "passive"))
      (node (ref "SW1") (pin "D") (pinfunction "D_D") (pintype "passive"))
      (node (ref "U2") (pin "37") (pinfunction "RESETIN_37") (pintype "input"))
    )
    (net (code "62") (name "/RREF_SS") (class "Default")
      (node (ref "R15") (pin "2") (pinfunction "2_2") (pintype "passive"))
      (node (ref "U2") (pin "32") (pinfunction "RREF_SS_32") (pintype "bidirectional"))
    )
    (net (code "63") (name "/RREF_USB2") (class "Default")
      (node (ref "R16") (pin "2") (pinfunction "2_2") (pintype "passive"))
      (node (ref "U2") (pin "7") (pinfunction "RREF_USB2_7") (pintype "bidirectional"))
    )
    (net (code "64") (name "/SUSPEND") (class "Default")
      (node (ref "D1") (pin "A") (pinfunction "A_A") (pintype "passive"))
      (node (ref "U2") (pin "25") (pinfunction "SUSPEND_25") (pintype "bidirectional"))
    )
    (net (code "65") (name "/US_D_N") (class "Default")
      (node (ref "U2") (pin "72") (pinfunction "US_DM_72") (pintype "bidirectional"))
      (node (ref "US") (pin "2") (pinfunction "DM_2") (pintype "bidirectional"))
    )
    (net (code "66") (name "/US_D_P") (class "Default")
      (node (ref "U2") (pin "71") (pinfunction "US_DP_71") (pintype "bidirectional"))
      (node (ref "US") (pin "3") (pinfunction "DP_3") (pintype "bidirectional"))
    )
    (net (code "67") (name "/US_N") (class "Default")
      (node (ref "C15") (pin "2") (pinfunction "2_2") (pintype "passive"))
      (node (ref "US") (pin "5") (pinfunction "SSTXM_5") (pintype "input"))
    )
    (net (code "68") (name "/US_OVRCURR") (class "Default")
      (node (ref "R21") (pin "1") (pinfunction "1_1") (pintype "passive"))
      (node (ref "U2") (pin "39") (pinfunction "US_OVRCURR_39") (pintype "input"))
    )
    (net (code "69") (name "/US_P") (class "Default")
      (node (ref "C17") (pin "2") (pinfunction "2_2") (pintype "passive"))
      (node (ref "US") (pin "6") (pinfunction "SSTXP_6") (pintype "input"))
    )
    (net (code "70") (name "/US_RX_N") (class "Default")
      (node (ref "U2") (pin "13") (pinfunction "US_RXM_13") (pintype "input"))
      (node (ref "US") (pin "8") (pinfunction "SSRXM_8") (pintype "output"))
    )
    (net (code "71") (name "/US_RX_P") (class "Default")
      (node (ref "U2") (pin "14") (pinfunction "US_RXP_14") (pintype "input"))
      (node (ref "US") (pin "9") (pinfunction "SSRXP_9") (pintype "output"))
    )
    (net (code "72") (name "/US_TX_N") (class "Default")
      (node (ref "C15") (pin "1") (pinfunction "1_1") (pintype "passive"))
      (node (ref "U2") (pin "10") (pinfunction "US_TXM_10") (pintype "output"))
    )
    (net (code "73") (name "/US_TX_P") (class "Default")
      (node (ref "C17") (pin "1") (pinfunction "1_1") (pintype "passive"))
      (node (ref "U2") (pin "11") (pinfunction "US_TXP_11") (pintype "output"))
    )
    (net (code "74") (name "/XTL_IN") (class "Default")
      (node (ref "C13") (pin "1") (pinfunction "1_1") (pintype "passive"))
      (node (ref "Q1") (pin "P$1") (pinfunction "1_P$1") (pintype "passive"))
      (node (ref "U2") (pin "69") (pinfunction "XTL_IN_69") (pintype "bidirectional"))
    )
    (net (code "75") (name "/XTL_OUT") (class "Default")
      (node (ref "C12") (pin "1") (pinfunction "1_1") (pintype "passive"))
      (node (ref "Q1") (pin "P$3") (pinfunction "2_P$3") (pintype "passive"))
      (node (ref "U2") (pin "68") (pinfunction "XTL_OUT_68") (pintype "bidirectional"))
    )
    (net (code "76") (name "GND") (class "Default")
      (node (ref "C1") (pin "2") (pinfunction "2_2") (pintype "passive"))
      (node (ref "C10") (pin "2") (pinfunction "2_2") (pintype "passive"))
      (node (ref "C11") (pin "2") (pinfunction "2_2") (pintype "passive"))
      (node (ref "C12") (pin "2") (pinfunction "2_2") (pintype "passive"))
      (node (ref "C13") (pin "2") (pinfunction "2_2") (pintype "passive"))
      (node (ref "C14") (pin "2") (pinfunction "2_2") (pintype "passive"))
      (node (ref "C16") (pin "2") (pinfunction "2_2") (pintype "passive"))
      (node (ref "C2") (pin "2") (pinfunction "2_2") (pintype "passive"))
      (node (ref "C20") (pin "2") (pinfunction "2_2") (pintype "passive"))
      (node (ref "C21") (pin "2") (pinfunction "2_2") (pintype "passive"))
      (node (ref "C3") (pin "2") (pinfunction "2_2") (pintype "passive"))
      (node (ref "C30") (pin "2") (pinfunction "2_2") (pintype "passive"))
      (node (ref "C31") (pin "2") (pinfunction "2_2") (pintype "passive"))
      (node (ref "C32") (pin "2") (pinfunction "2_2") (pintype "passive"))
      (node (ref "C33") (pin "2") (pinfunction "2_2") (pintype "passive"))
      (node (ref "C34") (pin "2") (pinfunction "2_2") (pintype "passive"))
      (node (ref "C4") (pin "2") (pinfunction "2_2") (pintype "passive"))
      (node (ref "C5") (pin "2") (pinfunction "2_2") (pintype "passive"))
      (node (ref "C6") (pin "2") (pinfunction "2_2") (pintype "passive"))
      (node (ref "C7") (pin "2") (pinfunction "2_2") (pintype "passive"))
      (node (ref "C8") (pin "2") (pinfunction "2_2") (pintype "passive"))
      (node (ref "C9") (pin "2") (pinfunction "2_2") (pintype "passive"))
      (node (ref "DS1") (pin "4") (pinfunction "GND_4") (pintype "power_in"))
      (node (ref "DS1") (pin "7") (pinfunction "GND_DRAIN_7") (pintype "power_in"))
      (node (ref "DS2") (pin "4") (pinfunction "GND_4") (pintype "power_in"))
      (node (ref "DS2") (pin "7") (pinfunction "GND_DRAIN_7") (pintype "power_in"))
      (node (ref "DS3") (pin "4") (pinfunction "GND_4") (pintype "power_in"))
      (node (ref "DS3") (pin "7") (pinfunction "GND_DRAIN_7") (pintype "power_in"))
      (node (ref "DS4") (pin "4") (pinfunction "GND_4") (pintype "power_in"))
      (node (ref "DS4") (pin "7") (pinfunction "GND_DRAIN_7") (pintype "power_in"))
      (node (ref "Q1") (pin "P$2") (pinfunction "GND_P$2") (pintype "power_in"))
      (node (ref "Q1") (pin "P$4") (pinfunction "GND_P$4") (pintype "power_in"))
      (node (ref "R10") (pin "2") (pinfunction "2_2") (pintype "passive"))
      (node (ref "R11") (pin "2") (pinfunction "2_2") (pintype "passive"))
      (node (ref "R12") (pin "2") (pinfunction "2_2") (pintype "passive"))
      (node (ref "R13") (pin "2") (pinfunction "2_2") (pintype "passive"))
      (node (ref "R14") (pin "2") (pinfunction "2_2") (pintype "passive"))
      (node (ref "R15") (pin "1") (pinfunction "1_1") (pintype "passive"))
      (node (ref "R16") (pin "1") (pinfunction "1_1") (pintype "passive"))
      (node (ref "R2") (pin "1") (pinfunction "1_1") (pintype "passive"))
      (node (ref "R26") (pin "2") (pinfunction "2_2") (pintype "passive"))
      (node (ref "R27") (pin "2") (pinfunction "2_2") (pintype "passive"))
      (node (ref "R28") (pin "2") (pinfunction "2_2") (pintype "passive"))
      (node (ref "R3") (pin "2") (pinfunction "2_2") (pintype "passive"))
      (node (ref "R31") (pin "2") (pinfunction "2_2") (pintype "passive"))
      (node (ref "R32") (pin "2") (pinfunction "2_2") (pintype "passive"))
      (node (ref "R33") (pin "2") (pinfunction "2_2") (pintype "passive"))
      (node (ref "R34") (pin "2") (pinfunction "2_2") (pintype "passive"))
      (node (ref "R35") (pin "2") (pinfunction "2_2") (pintype "passive"))
      (node (ref "R36") (pin "1") (pinfunction "1_1") (pintype "passive"))
      (node (ref "R4") (pin "2") (pinfunction "2_2") (pintype "passive"))
      (node (ref "R41") (pin "1") (pinfunction "1_1") (pintype "passive"))
      (node (ref "R42") (pin "1") (pinfunction "1_1") (pintype "passive"))
      (node (ref "R43") (pin "1") (pinfunction "1_1") (pintype "passive"))
      (node (ref "R44") (pin "1") (pinfunction "1_1") (pintype "passive"))
      (node (ref "R45") (pin "1") (pinfunction "1_1") (pintype "passive"))
      (node (ref "R47") (pin "2") (pinfunction "2_2") (pintype "passive"))
      (node (ref "R5") (pin "2") (pinfunction "2_2") (pintype "passive"))
      (node (ref "R6") (pin "2") (pinfunction "2_2") (pintype "passive"))
      (node (ref "R7") (pin "2") (pinfunction "2_2") (pintype "passive"))
      (node (ref "R8") (pin "2") (pinfunction "2_2") (pintype "passive"))
      (node (ref "R9") (pin "2") (pinfunction "2_2") (pintype "passive"))
      (node (ref "SW1") (pin "A") (pinfunction "A_A") (pintype "passive"))
      (node (ref "U1") (pin "2") (pinfunction "GND_2") (pintype "power_in"))
      (node (ref "U2") (pin "50") (pinfunction "GND_50") (pintype "power_in"))
      (node (ref "U2") (pin "89") (pinfunction "EPAD_89") (pintype "power_in"))
      (node (ref "U3") (pin "2") (pinfunction "GND_2") (pintype "power_in"))
      (node (ref "US") (pin "4") (pinfunction "GND_4") (pintype "power_in"))
      (node (ref "US") (pin "7") (pinfunction "GND_DRAIN_7") (pintype "power_in"))
    )
    (net (code "77") (name "Net-(C30-Pad1)") (class "Default")
      (node (ref "C30") (pin "1") (pinfunction "1_1") (pintype "passive"))
      (node (ref "R41") (pin "2") (pinfunction "2_2") (pintype "passive"))
      (node (ref "US") (pin "SHIELD1") (pinfunction "SHIELD_SHIELD1") (pintype "power_in"))
      (node (ref "US") (pin "SHIELD2") (pinfunction "SHIELD_SHIELD2") (pintype "power_in"))
    )
    (net (code "78") (name "Net-(C31-Pad1)") (class "Default")
      (node (ref "C31") (pin "1") (pinfunction "1_1") (pintype "passive"))
      (node (ref "DS1") (pin "SHIELD1") (pinfunction "SHIELD_SHIELD1") (pintype "power_in"))
      (node (ref "DS1") (pin "SHIELD2") (pinfunction "SHIELD_SHIELD2") (pintype "power_in"))
      (node (ref "R42") (pin "2") (pinfunction "2_2") (pintype "passive"))
    )
    (net (code "79") (name "Net-(C32-Pad1)") (class "Default")
      (node (ref "C32") (pin "1") (pinfunction "1_1") (pintype "passive"))
      (node (ref "DS2") (pin "SHIELD1") (pinfunction "SHIELD_SHIELD1") (pintype "power_in"))
      (node (ref "DS2") (pin "SHIELD2") (pinfunction "SHIELD_SHIELD2") (pintype "power_in"))
      (node (ref "R43") (pin "2") (pinfunction "2_2") (pintype "passive"))
    )
    (net (code "80") (name "Net-(C33-Pad1)") (class "Default")
      (node (ref "C33") (pin "1") (pinfunction "1_1") (pintype "passive"))
      (node (ref "DS3") (pin "SHIELD1") (pinfunction "SHIELD_SHIELD1") (pintype "power_in"))
      (node (ref "DS3") (pin "SHIELD2") (pinfunction "SHIELD_SHIELD2") (pintype "power_in"))
      (node (ref "R44") (pin "2") (pinfunction "2_2") (pintype "passive"))
    )
    (net (code "81") (name "Net-(C34-Pad1)") (class "Default")
      (node (ref "C34") (pin "1") (pinfunction "1_1") (pintype "passive"))
      (node (ref "DS4") (pin "SHIELD1") (pinfunction "SHIELD_SHIELD1") (pintype "power_in"))
      (node (ref "DS4") (pin "SHIELD2") (pinfunction "SHIELD_SHIELD2") (pintype "power_in"))
      (node (ref "R45") (pin "2") (pinfunction "2_2") (pintype "passive"))
    )
    (net (code "82") (name "Net-(D1-PadC)") (class "Default")
      (node (ref "D1") (pin "C") (pinfunction "C_C") (pintype "passive"))
      (node (ref "R2") (pin "2") (pinfunction "2_2") (pintype "passive"))
    )
    (net (code "83") (name "Net-(D2-PadC)") (class "Default")
      (node (ref "D2") (pin "C") (pinfunction "C_C") (pintype "passive"))
      (node (ref "R9") (pin "1") (pinfunction "1_1") (pintype "passive"))
    )
    (net (code "84") (name "Net-(D3-PadC)") (class "Default")
      (node (ref "D3") (pin "C") (pinfunction "C_C") (pintype "passive"))
      (node (ref "R10") (pin "1") (pinfunction "1_1") (pintype "passive"))
    )
    (net (code "85") (name "Net-(D4-PadC)") (class "Default")
      (node (ref "D4") (pin "C") (pinfunction "C_C") (pintype "passive"))
      (node (ref "R11") (pin "1") (pinfunction "1_1") (pintype "passive"))
    )
    (net (code "86") (name "Net-(D5-PadC)") (class "Default")
      (node (ref "D5") (pin "C") (pinfunction "C_C") (pintype "passive"))
      (node (ref "R12") (pin "1") (pinfunction "1_1") (pintype "passive"))
    )
    (net (code "87") (name "Net-(D6-PadC)") (class "Default")
      (node (ref "D6") (pin "C") (pinfunction "C_C") (pintype "passive"))
      (node (ref "R13") (pin "1") (pinfunction "1_1") (pintype "passive"))
    )
    (net (code "88") (name "Net-(D7-PadC)") (class "Default")
      (node (ref "D7") (pin "C") (pinfunction "C_C") (pintype "passive"))
      (node (ref "R14") (pin "1") (pinfunction "1_1") (pintype "passive"))
    )
    (net (code "89") (name "Net-(D8-PadA)") (class "Default")
      (node (ref "D8") (pin "A") (pinfunction "A_A") (pintype "passive"))
      (node (ref "R17") (pin "1") (pinfunction "1_1") (pintype "passive"))
    )
    (net (code "90") (name "Net-(D9-PadA)") (class "Default")
      (node (ref "D9") (pin "A") (pinfunction "A_A") (pintype "passive"))
      (node (ref "R18") (pin "1") (pinfunction "1_1") (pintype "passive"))
    )
    (net (code "91") (name "Net-(D10-PadA)") (class "Default")
      (node (ref "D10") (pin "A") (pinfunction "A_A") (pintype "passive"))
      (node (ref "R19") (pin "1") (pinfunction "1_1") (pintype "passive"))
    )
    (net (code "92") (name "Net-(D11-PadA)") (class "Default")
      (node (ref "D11") (pin "A") (pinfunction "A_A") (pintype "passive"))
      (node (ref "R20") (pin "1") (pinfunction "1_1") (pintype "passive"))
    )
    (net (code "93") (name "Net-(D12-PadC)") (class "Default")
      (node (ref "D12") (pin "C") (pinfunction "C_C") (pintype "passive"))
      (node (ref "R27") (pin "1") (pinfunction "1_1") (pintype "passive"))
    )
    (net (code "94") (name "Net-(D13-PadC)") (class "Default")
      (node (ref "D13") (pin "C") (pinfunction "C_C") (pintype "passive"))
      (node (ref "R28") (pin "1") (pinfunction "1_1") (pintype "passive"))
    )
    (net (code "95") (name "Net-(D14-PadC)") (class "Default")
      (node (ref "D14") (pin "C") (pinfunction "C_C") (pintype "passive"))
      (node (ref "R36") (pin "2") (pinfunction "2_2") (pintype "passive"))
    )
    (net (code "96") (name "Net-(L1-1)") (class "Default")
      (node (ref "L1") (pin "P$1") (pinfunction "1_P$1") (pintype "passive"))
      (node (ref "U1") (pin "3") (pinfunction "LX_3") (pintype "output"))
    )
    (net (code "97") (name "Net-(L2-1)") (class "Default")
      (node (ref "L2") (pin "P$1") (pinfunction "1_P$1") (pintype "passive"))
      (node (ref "U3") (pin "5") (pinfunction "SW_5") (pintype "output"))
    )
    (net (code "98") (name "Net-(U2-VBUS_US)") (class "Default")
      (node (ref "R46") (pin "1") (pinfunction "1_1") (pintype "passive"))
      (node (ref "R47") (pin "1") (pinfunction "1_1") (pintype "passive"))
      (node (ref "U2") (pin "22") (pinfunction "VBUS_US_22") (pintype "power_in"))
    )
    (net (code "99") (name "unconnected-(SW1-PadB)") (class "Default")
      (node (ref "SW1") (pin "B") (pinfunction "B_B") (pintype "passive"))
    )
    (net (code "100") (name "unconnected-(SW1-PadC)") (class "Default")
      (node (ref "SW1") (pin "C") (pinfunction "C_C") (pintype "passive"))
    )
  )
)
